# 2.net
KiCad netlist of a schematic drawn in Altium Designer
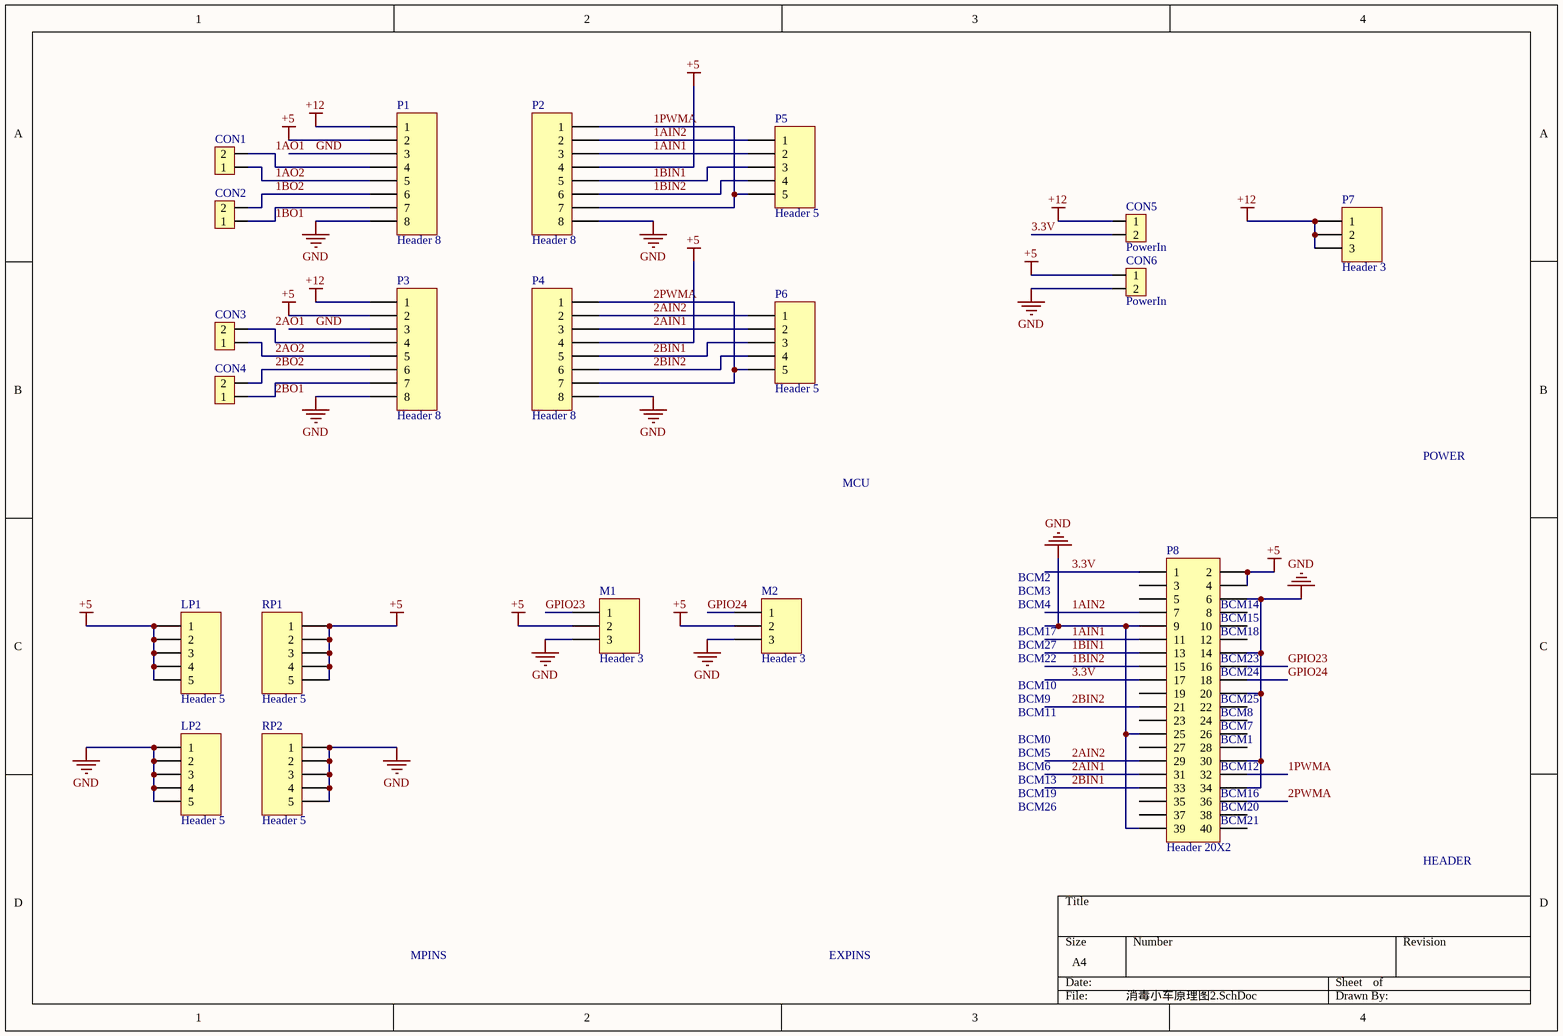
[diagram p0: 消毒小车原理图2.SchDoc]

(export (version "E")
  (design (tool "Eeschema 10.0.6"))
  (components
    (comp (ref "CON1")
      (value "PowerIn")
      (footprint "KF301-2P")
      (description "Header, 2-Pin")
      (libsource (lib "MOS motor driving module ") (part "Header 2"))
    )
    (comp (ref "CON2")
      (value "PowerIn")
      (footprint "KF301-2P")
      (description "Header, 2-Pin")
      (libsource (lib "MOS motor driving module ") (part "Header 2"))
    )
    (comp (ref "CON3")
      (value "PowerIn")
      (footprint "KF301-2P")
      (description "Header, 2-Pin")
      (libsource (lib "MOS motor driving module ") (part "Header 2"))
    )
    (comp (ref "CON4")
      (value "PowerIn")
      (footprint "KF301-2P")
      (description "Header, 2-Pin")
      (libsource (lib "MOS motor driving module ") (part "Header 2"))
    )
    (comp (ref "CON5")
      (value "PowerIn")
      (footprint "KF301-2P")
      (description "Header, 2-Pin")
      (libsource (lib "") (part "Header 2_1"))
    )
    (comp (ref "CON6")
      (value "PowerIn")
      (footprint "KF301-2P")
      (description "Header, 2-Pin")
      (libsource (lib "") (part "Header 2_1"))
    )
    (comp (ref "LP1")
      (value "Header 5")
      (footprint "HDR1X5")
      (description "Header, 5-Pin")
      (fields (field (name "PUBLISHER") "Altium Limited"))
      (libsource (lib "Miscellaneous Connectors") (part "Header 5"))
    )
    (comp (ref "LP2")
      (value "Header 5")
      (footprint "HDR1X5")
      (description "Header, 5-Pin")
      (fields (field (name "PUBLISHER") "Altium Limited"))
      (libsource (lib "Miscellaneous Connectors") (part "Header 5"))
    )
    (comp (ref "M1")
      (value "Header 3")
      (footprint "HDR1X3")
      (description "Header, 3-Pin")
      (fields (field (name "PUBLISHER") "Altium Limited"))
      (libsource (lib "Miscellaneous Connectors") (part "Header 3"))
    )
    (comp (ref "M2")
      (value "Header 3")
      (footprint "HDR1X3")
      (description "Header, 3-Pin")
      (fields (field (name "PUBLISHER") "Altium Limited"))
      (libsource (lib "Miscellaneous Connectors") (part "Header 3"))
    )
    (comp (ref "P1")
      (value "Header 8")
      (footprint "HDR1X8")
      (description "Header, 8-Pin")
      (fields (field (name "PUBLISHER") "Altium Limited"))
      (libsource (lib "Miscellaneous Connectors") (part "Header 8"))
    )
    (comp (ref "P2")
      (value "Header 8")
      (footprint "HDR1X8")
      (description "Header, 8-Pin")
      (fields (field (name "PUBLISHER") "Altium Limited"))
      (libsource (lib "") (part "Header 8_1"))
    )
    (comp (ref "P3")
      (value "Header 8")
      (footprint "HDR1X8")
      (description "Header, 8-Pin")
      (fields (field (name "PUBLISHER") "Altium Limited"))
      (libsource (lib "Miscellaneous Connectors") (part "Header 8"))
    )
    (comp (ref "P4")
      (value "Header 8")
      (footprint "HDR1X8")
      (description "Header, 8-Pin")
      (fields (field (name "PUBLISHER") "Altium Limited"))
      (libsource (lib "") (part "Header 8_1"))
    )
    (comp (ref "P5")
      (value "Header 5")
      (footprint "HDR1X5")
      (description "Header, 5-Pin")
      (fields (field (name "PUBLISHER") "Altium Limited"))
      (libsource (lib "Miscellaneous Connectors") (part "Header 5"))
    )
    (comp (ref "P6")
      (value "Header 5")
      (footprint "HDR1X5")
      (description "Header, 5-Pin")
      (fields (field (name "PUBLISHER") "Altium Limited"))
      (libsource (lib "Miscellaneous Connectors") (part "Header 5"))
    )
    (comp (ref "P7")
      (value "Header 3")
      (footprint "HDR1X3")
      (description "Header, 3-Pin")
      (fields (field (name "PUBLISHER") "Altium Limited"))
      (libsource (lib "Miscellaneous Connectors") (part "Header 3"))
    )
    (comp (ref "P8")
      (value "Header 20X2")
      (footprint "HDR2X20")
      (description "Header, 20-Pin, Dual row")
      (fields (field (name "PUBLISHER") "Altium Limited"))
      (libsource (lib "Miscellaneous Connectors") (part "Header 20X2"))
    )
    (comp (ref "RP1")
      (value "Header 5")
      (footprint "HDR1X5")
      (description "Header, 5-Pin")
      (fields (field (name "PUBLISHER") "Altium Limited"))
      (libsource (lib "") (part "Header 5_1"))
    )
    (comp (ref "RP2")
      (value "Header 5")
      (footprint "HDR1X5")
      (description "Header, 5-Pin")
      (fields (field (name "PUBLISHER") "Altium Limited"))
      (libsource (lib "") (part "Header 5_1"))
    )
  )
  (nets
    (net (code "1") (name "+5") (class "Default")
      (node (ref "CON6") (pin "1") (pinfunction "1_1") (pintype "passive"))
      (node (ref "LP1") (pin "1") (pinfunction "1_1") (pintype "passive"))
      (node (ref "LP1") (pin "2") (pinfunction "2_2") (pintype "passive"))
      (node (ref "LP1") (pin "3") (pinfunction "3_3") (pintype "passive"))
      (node (ref "LP1") (pin "4") (pinfunction "4_4") (pintype "passive"))
      (node (ref "LP1") (pin "5") (pinfunction "5_5") (pintype "passive"))
      (node (ref "M1") (pin "2") (pinfunction "2_2") (pintype "passive"))
      (node (ref "M2") (pin "2") (pinfunction "2_2") (pintype "passive"))
      (node (ref "P1") (pin "2") (pinfunction "2_2") (pintype "passive"))
      (node (ref "P2") (pin "4") (pinfunction "4_4") (pintype "passive"))
      (node (ref "P3") (pin "2") (pinfunction "2_2") (pintype "passive"))
      (node (ref "P4") (pin "4") (pinfunction "4_4") (pintype "passive"))
      (node (ref "P8") (pin "2") (pinfunction "2_2") (pintype "passive"))
      (node (ref "P8") (pin "4") (pinfunction "4_4") (pintype "passive"))
      (node (ref "RP1") (pin "1") (pinfunction "1_1") (pintype "passive"))
      (node (ref "RP1") (pin "2") (pinfunction "2_2") (pintype "passive"))
      (node (ref "RP1") (pin "3") (pinfunction "3_3") (pintype "passive"))
      (node (ref "RP1") (pin "4") (pinfunction "4_4") (pintype "passive"))
      (node (ref "RP1") (pin "5") (pinfunction "5_5") (pintype "passive"))
    )
    (net (code "2") (name "+12") (class "Default")
      (node (ref "CON5") (pin "1") (pinfunction "1_1") (pintype "passive"))
      (node (ref "P1") (pin "1") (pinfunction "1_1") (pintype "passive"))
      (node (ref "P3") (pin "1") (pinfunction "1_1") (pintype "passive"))
      (node (ref "P7") (pin "1") (pinfunction "1_1") (pintype "passive"))
      (node (ref "P7") (pin "2") (pinfunction "2_2") (pintype "passive"))
      (node (ref "P7") (pin "3") (pinfunction "3_3") (pintype "passive"))
    )
    (net (code "3") (name "/1AIN1") (class "Default")
      (node (ref "P2") (pin "3") (pinfunction "3_3") (pintype "passive"))
      (node (ref "P5") (pin "2") (pinfunction "2_2") (pintype "passive"))
      (node (ref "P8") (pin "11") (pinfunction "11_11") (pintype "passive"))
    )
    (net (code "4") (name "/1AIN2") (class "Default")
      (node (ref "P2") (pin "2") (pinfunction "2_2") (pintype "passive"))
      (node (ref "P5") (pin "1") (pinfunction "1_1") (pintype "passive"))
      (node (ref "P8") (pin "7") (pinfunction "7_7") (pintype "passive"))
    )
    (net (code "5") (name "/1AO1") (class "Default")
      (node (ref "CON1") (pin "2") (pinfunction "2_2") (pintype "passive"))
      (node (ref "P1") (pin "4") (pinfunction "4_4") (pintype "passive"))
    )
    (net (code "6") (name "/1AO2") (class "Default")
      (node (ref "CON1") (pin "1") (pinfunction "1_1") (pintype "passive"))
      (node (ref "P1") (pin "5") (pinfunction "5_5") (pintype "passive"))
    )
    (net (code "7") (name "/1BIN1") (class "Default")
      (node (ref "P2") (pin "5") (pinfunction "5_5") (pintype "passive"))
      (node (ref "P5") (pin "3") (pinfunction "3_3") (pintype "passive"))
      (node (ref "P8") (pin "13") (pinfunction "13_13") (pintype "passive"))
    )
    (net (code "8") (name "/1BIN2") (class "Default")
      (node (ref "P2") (pin "6") (pinfunction "6_6") (pintype "passive"))
      (node (ref "P5") (pin "4") (pinfunction "4_4") (pintype "passive"))
      (node (ref "P8") (pin "15") (pinfunction "15_15") (pintype "passive"))
    )
    (net (code "9") (name "/1BO1") (class "Default")
      (node (ref "CON2") (pin "1") (pinfunction "1_1") (pintype "passive"))
      (node (ref "P1") (pin "7") (pinfunction "7_7") (pintype "passive"))
    )
    (net (code "10") (name "/1BO2") (class "Default")
      (node (ref "CON2") (pin "2") (pinfunction "2_2") (pintype "passive"))
      (node (ref "P1") (pin "6") (pinfunction "6_6") (pintype "passive"))
    )
    (net (code "11") (name "/1PWMA") (class "Default")
      (node (ref "P2") (pin "1") (pinfunction "1_1") (pintype "passive"))
      (node (ref "P2") (pin "7") (pinfunction "7_7") (pintype "passive"))
      (node (ref "P5") (pin "5") (pinfunction "5_5") (pintype "passive"))
      (node (ref "P8") (pin "32") (pinfunction "32_32") (pintype "passive"))
    )
    (net (code "12") (name "/2AIN1") (class "Default")
      (node (ref "P4") (pin "3") (pinfunction "3_3") (pintype "passive"))
      (node (ref "P6") (pin "2") (pinfunction "2_2") (pintype "passive"))
      (node (ref "P8") (pin "31") (pinfunction "31_31") (pintype "passive"))
    )
    (net (code "13") (name "/2AIN2") (class "Default")
      (node (ref "P4") (pin "2") (pinfunction "2_2") (pintype "passive"))
      (node (ref "P6") (pin "1") (pinfunction "1_1") (pintype "passive"))
      (node (ref "P8") (pin "29") (pinfunction "29_29") (pintype "passive"))
    )
    (net (code "14") (name "/2AO1") (class "Default")
      (node (ref "CON3") (pin "2") (pinfunction "2_2") (pintype "passive"))
      (node (ref "P3") (pin "4") (pinfunction "4_4") (pintype "passive"))
    )
    (net (code "15") (name "/2AO2") (class "Default")
      (node (ref "CON3") (pin "1") (pinfunction "1_1") (pintype "passive"))
      (node (ref "P3") (pin "5") (pinfunction "5_5") (pintype "passive"))
    )
    (net (code "16") (name "/2BIN1") (class "Default")
      (node (ref "P4") (pin "5") (pinfunction "5_5") (pintype "passive"))
      (node (ref "P6") (pin "3") (pinfunction "3_3") (pintype "passive"))
      (node (ref "P8") (pin "33") (pinfunction "33_33") (pintype "passive"))
    )
    (net (code "17") (name "/2BIN2") (class "Default")
      (node (ref "P4") (pin "6") (pinfunction "6_6") (pintype "passive"))
      (node (ref "P6") (pin "4") (pinfunction "4_4") (pintype "passive"))
      (node (ref "P8") (pin "21") (pinfunction "21_21") (pintype "passive"))
    )
    (net (code "18") (name "/2BO1") (class "Default")
      (node (ref "CON4") (pin "1") (pinfunction "1_1") (pintype "passive"))
      (node (ref "P3") (pin "7") (pinfunction "7_7") (pintype "passive"))
    )
    (net (code "19") (name "/2BO2") (class "Default")
      (node (ref "CON4") (pin "2") (pinfunction "2_2") (pintype "passive"))
      (node (ref "P3") (pin "6") (pinfunction "6_6") (pintype "passive"))
    )
    (net (code "20") (name "/2PWMA") (class "Default")
      (node (ref "P4") (pin "1") (pinfunction "1_1") (pintype "passive"))
      (node (ref "P4") (pin "7") (pinfunction "7_7") (pintype "passive"))
      (node (ref "P6") (pin "5") (pinfunction "5_5") (pintype "passive"))
      (node (ref "P8") (pin "36") (pinfunction "36_36") (pintype "passive"))
    )
    (net (code "21") (name "/3.3V") (class "Default")
      (node (ref "CON5") (pin "2") (pinfunction "2_2") (pintype "passive"))
      (node (ref "P8") (pin "1") (pinfunction "1_1") (pintype "passive"))
      (node (ref "P8") (pin "17") (pinfunction "17_17") (pintype "passive"))
    )
    (net (code "23") (name "/GPIO23") (class "Default")
      (node (ref "M1") (pin "1") (pinfunction "1_1") (pintype "passive"))
      (node (ref "P8") (pin "16") (pinfunction "16_16") (pintype "passive"))
    )
    (net (code "24") (name "/GPIO24") (class "Default")
      (node (ref "M2") (pin "1") (pinfunction "1_1") (pintype "passive"))
      (node (ref "P8") (pin "18") (pinfunction "18_18") (pintype "passive"))
    )
    (net (code "25") (name "GND") (class "Default")
      (node (ref "CON6") (pin "2") (pinfunction "2_2") (pintype "passive"))
      (node (ref "LP2") (pin "1") (pinfunction "1_1") (pintype "passive"))
      (node (ref "LP2") (pin "2") (pinfunction "2_2") (pintype "passive"))
      (node (ref "LP2") (pin "3") (pinfunction "3_3") (pintype "passive"))
      (node (ref "LP2") (pin "4") (pinfunction "4_4") (pintype "passive"))
      (node (ref "LP2") (pin "5") (pinfunction "5_5") (pintype "passive"))
      (node (ref "M1") (pin "3") (pinfunction "3_3") (pintype "passive"))
      (node (ref "M2") (pin "3") (pinfunction "3_3") (pintype "passive"))
      (node (ref "P1") (pin "3") (pinfunction "3_3") (pintype "passive"))
      (node (ref "P1") (pin "8") (pinfunction "8_8") (pintype "passive"))
      (node (ref "P2") (pin "8") (pinfunction "8_8") (pintype "passive"))
      (node (ref "P3") (pin "3") (pinfunction "3_3") (pintype "passive"))
      (node (ref "P3") (pin "8") (pinfunction "8_8") (pintype "passive"))
      (node (ref "P4") (pin "8") (pinfunction "8_8") (pintype "passive"))
      (node (ref "P8") (pin "14") (pinfunction "14_14") (pintype "passive"))
      (node (ref "P8") (pin "20") (pinfunction "20_20") (pintype "passive"))
      (node (ref "P8") (pin "25") (pinfunction "25_25") (pintype "passive"))
      (node (ref "P8") (pin "30") (pinfunction "30_30") (pintype "passive"))
      (node (ref "P8") (pin "34") (pinfunction "34_34") (pintype "passive"))
      (node (ref "P8") (pin "39") (pinfunction "39_39") (pintype "passive"))
      (node (ref "P8") (pin "6") (pinfunction "6_6") (pintype "passive"))
      (node (ref "P8") (pin "9") (pinfunction "9_9") (pintype "passive"))
      (node (ref "RP2") (pin "1") (pinfunction "1_1") (pintype "passive"))
      (node (ref "RP2") (pin "2") (pinfunction "2_2") (pintype "passive"))
      (node (ref "RP2") (pin "3") (pinfunction "3_3") (pintype "passive"))
      (node (ref "RP2") (pin "4") (pinfunction "4_4") (pintype "passive"))
      (node (ref "RP2") (pin "5") (pinfunction "5_5") (pintype "passive"))
    )
    (net (code "26") (name "unconnected-(P8-Pad3)") (class "Default")
      (node (ref "P8") (pin "3") (pinfunction "3_3") (pintype "passive"))
    )
    (net (code "27") (name "unconnected-(P8-Pad5)") (class "Default")
      (node (ref "P8") (pin "5") (pinfunction "5_5") (pintype "passive"))
    )
    (net (code "28") (name "unconnected-(P8-Pad8)") (class "Default")
      (node (ref "P8") (pin "8") (pinfunction "8_8") (pintype "passive"))
    )
    (net (code "29") (name "unconnected-(P8-Pad10)") (class "Default")
      (node (ref "P8") (pin "10") (pinfunction "10_10") (pintype "passive"))
    )
    (net (code "30") (name "unconnected-(P8-Pad12)") (class "Default")
      (node (ref "P8") (pin "12") (pinfunction "12_12") (pintype "passive"))
    )
    (net (code "31") (name "unconnected-(P8-Pad19)") (class "Default")
      (node (ref "P8") (pin "19") (pinfunction "19_19") (pintype "passive"))
    )
    (net (code "32") (name "unconnected-(P8-Pad22)") (class "Default")
      (node (ref "P8") (pin "22") (pinfunction "22_22") (pintype "passive"))
    )
    (net (code "33") (name "unconnected-(P8-Pad23)") (class "Default")
      (node (ref "P8") (pin "23") (pinfunction "23_23") (pintype "passive"))
    )
    (net (code "34") (name "unconnected-(P8-Pad24)") (class "Default")
      (node (ref "P8") (pin "24") (pinfunction "24_24") (pintype "passive"))
    )
    (net (code "35") (name "unconnected-(P8-Pad26)") (class "Default")
      (node (ref "P8") (pin "26") (pinfunction "26_26") (pintype "passive"))
    )
    (net (code "36") (name "unconnected-(P8-Pad27)") (class "Default")
      (node (ref "P8") (pin "27") (pinfunction "27_27") (pintype "passive"))
    )
    (net (code "37") (name "unconnected-(P8-Pad28)") (class "Default")
      (node (ref "P8") (pin "28") (pinfunction "28_28") (pintype "passive"))
    )
    (net (code "38") (name "unconnected-(P8-Pad35)") (class "Default")
      (node (ref "P8") (pin "35") (pinfunction "35_35") (pintype "passive"))
    )
    (net (code "39") (name "unconnected-(P8-Pad37)") (class "Default")
      (node (ref "P8") (pin "37") (pinfunction "37_37") (pintype "passive"))
    )
    (net (code "40") (name "unconnected-(P8-Pad38)") (class "Default")
      (node (ref "P8") (pin "38") (pinfunction "38_38") (pintype "passive"))
    )
    (net (code "41") (name "unconnected-(P8-Pad40)") (class "Default")
      (node (ref "P8") (pin "40") (pinfunction "40_40") (pintype "passive"))
    )
  )
)
